# Schematic.net
KiCad netlist of a schematic drawn in EAGLE
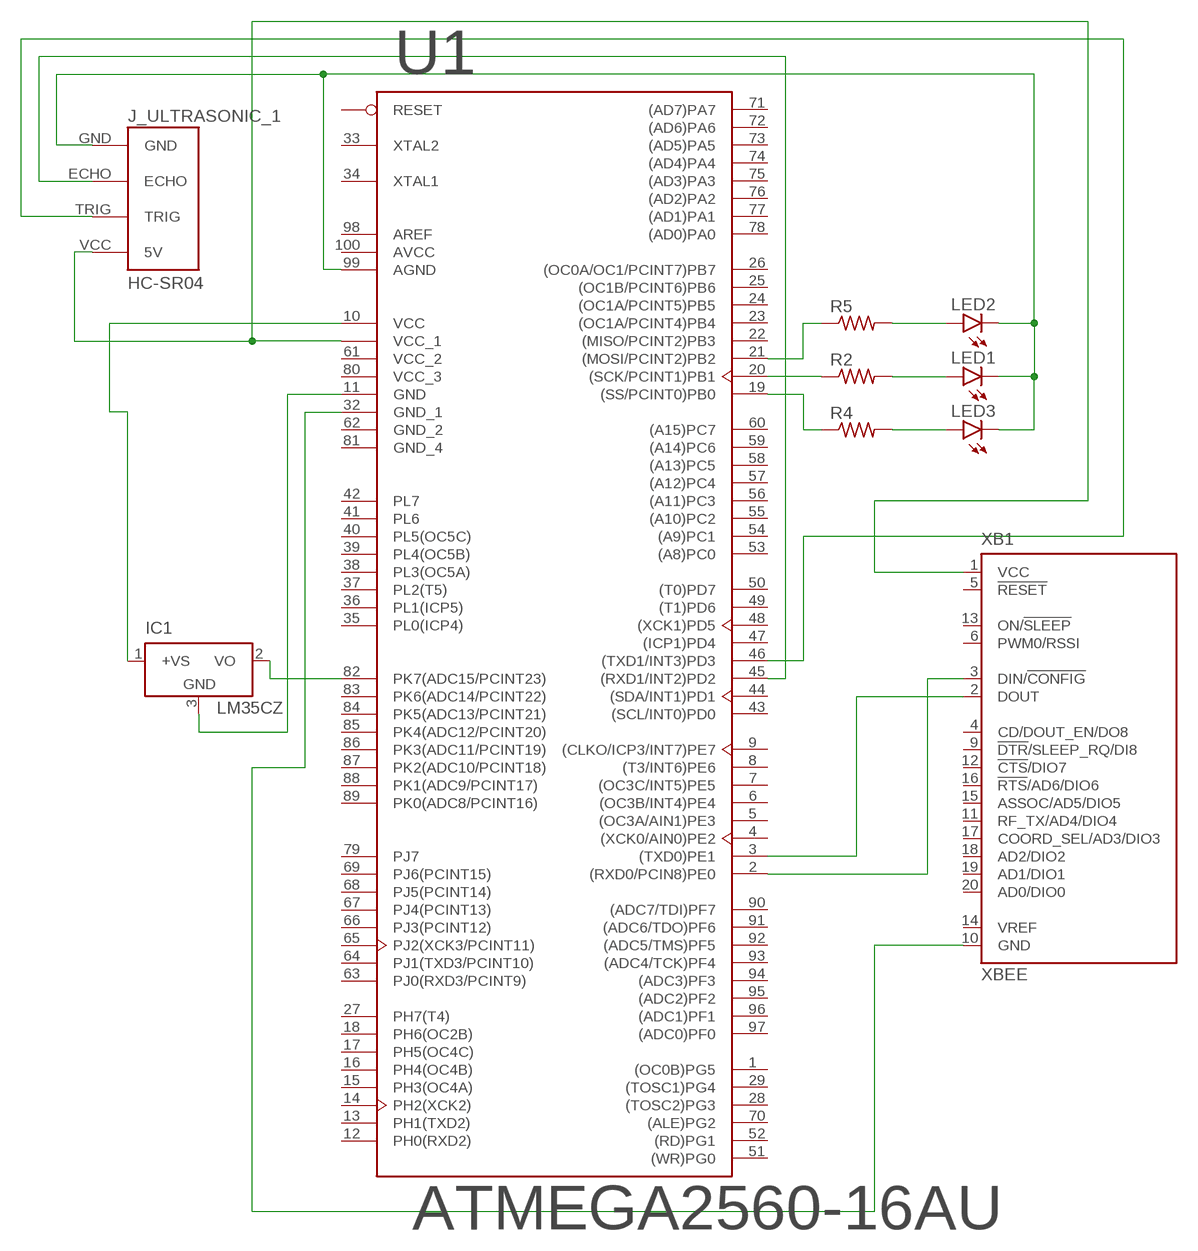
[diagram p0: schematic, sheet 1]

(export (version "E")
  (design (tool "Eeschema 10.0.6"))
  (components
    (comp (ref "IC1")
      (value "LM35CZ")
      (footprint "eagle-import:TO92")
      (libsource (lib "eagle-import") (part "LM35CZ"))
    )
    (comp (ref "J_ULTRASONIC_1")
      (value "HC-SR04")
      (footprint "eagle-import:HC-SR04_FOOTPRINT")
      (libsource (lib "eagle-import") (part "HC-SR04"))
    )
    (comp (ref "LED1")
      (value "LED5MM")
      (footprint "eagle-import:LED5MM")
      (libsource (lib "eagle-import") (part "LED5MM"))
    )
    (comp (ref "LED2")
      (value "LED5MM")
      (footprint "eagle-import:LED5MM")
      (libsource (lib "eagle-import") (part "LED5MM"))
    )
    (comp (ref "LED3")
      (value "LED5MM")
      (footprint "eagle-import:LED5MM")
      (libsource (lib "eagle-import") (part "LED5MM"))
    )
    (comp (ref "R2")
      (value "R-US_0204/7")
      (footprint "eagle-import:0204_7")
      (libsource (lib "eagle-import") (part "R-US_0204/7"))
    )
    (comp (ref "R4")
      (value "R-US_0204/7")
      (footprint "eagle-import:0204_7")
      (libsource (lib "eagle-import") (part "R-US_0204/7"))
    )
    (comp (ref "R5")
      (value "R-US_0204/7")
      (footprint "eagle-import:0204_7")
      (libsource (lib "eagle-import") (part "R-US_0204/7"))
    )
    (comp (ref "U1")
      (value "ATMEGA2560-16AU")
      (footprint "eagle-import:TQFP-100")
      (fields
        (field (name "DIGIKEY_PART_NUMBER") "ATMEGA2560-16AU-ND")
        (field (name "MANUFACTURER") "Microchip Technology")
        (field (name "CREATED_BY") "PCBLayout.com")
      )
      (libsource (lib "eagle-import") (part "ATMEGA2560-16AU"))
    )
    (comp (ref "XB1")
      (value "XBEE")
      (footprint "eagle-import:XBEE")
      (fields (field (name "MPN") "XBP24-Z7UIT-004"))
      (libsource (lib "eagle-import") (part "XBEE"))
    )
  )
  (nets
    (net (code "1") (name "/AREF") (class "Default")
      (node (ref "U1") (pin "98") (pinfunction "AREF_98") (pintype "power_in"))
    )
    (net (code "2") (name "/AVCC") (class "Default")
      (node (ref "U1") (pin "100") (pinfunction "AVCC_100") (pintype "power_in"))
    )
    (net (code "3") (name "/GND_2") (class "Default")
      (node (ref "U1") (pin "62") (pinfunction "GND_2_62") (pintype "power_in"))
    )
    (net (code "4") (name "/GND_4") (class "Default")
      (node (ref "U1") (pin "81") (pinfunction "GND_4_81") (pintype "power_in"))
    )
    (net (code "5") (name "/RESET") (class "Default")
      (node (ref "U1") (pin "30") (pinfunction "RESET_30") (pintype "power_in"))
    )
    (net (code "6") (name "/VCC_2") (class "Default")
      (node (ref "U1") (pin "61") (pinfunction "VCC_2_61") (pintype "power_in"))
    )
    (net (code "7") (name "/VCC_3") (class "Default")
      (node (ref "U1") (pin "80") (pinfunction "VCC_3_80") (pintype "power_in"))
    )
    (net (code "8") (name "Net-(IC1-+VS)") (class "Default")
      (node (ref "IC1") (pin "1") (pinfunction "+VS_1") (pintype "input"))
      (node (ref "U1") (pin "10") (pinfunction "VCC_10") (pintype "power_in"))
    )
    (net (code "9") (name "Net-(IC1-GND)") (class "Default")
      (node (ref "IC1") (pin "3") (pinfunction "GND_3") (pintype "power_in"))
      (node (ref "U1") (pin "11") (pinfunction "GND_11") (pintype "power_in"))
    )
    (net (code "10") (name "Net-(IC1-VO)") (class "Default")
      (node (ref "IC1") (pin "2") (pinfunction "VO_2") (pintype "input"))
      (node (ref "U1") (pin "82") (pinfunction "PK7(ADC15/PCINT23)_82") (pintype "bidirectional"))
    )
    (net (code "11") (name "Net-(J_ULTRASONIC_1-5V)") (class "Default")
      (node (ref "J_ULTRASONIC_1") (pin "VCC") (pinfunction "5V_VCC") (pintype "bidirectional"))
      (node (ref "U1") (pin "31") (pinfunction "VCC_1_31") (pintype "power_in"))
      (node (ref "XB1") (pin "1") (pinfunction "VCC_1") (pintype "power_in"))
    )
    (net (code "12") (name "Net-(LED1-C)") (class "Default")
      (node (ref "J_ULTRASONIC_1") (pin "GND") (pinfunction "GND_GND") (pintype "bidirectional"))
      (node (ref "LED1") (pin "K") (pinfunction "C_K") (pintype "passive"))
      (node (ref "LED2") (pin "K") (pinfunction "C_K") (pintype "passive"))
      (node (ref "LED3") (pin "K") (pinfunction "C_K") (pintype "passive"))
      (node (ref "U1") (pin "99") (pinfunction "AGND_99") (pintype "power_in"))
    )
    (net (code "13") (name "Net-(LED1-PadA)") (class "Default")
      (node (ref "LED1") (pin "A") (pinfunction "A_A") (pintype "passive"))
      (node (ref "R2") (pin "2") (pinfunction "2_2") (pintype "passive"))
    )
    (net (code "14") (name "Net-(LED2-PadA)") (class "Default")
      (node (ref "LED2") (pin "A") (pinfunction "A_A") (pintype "passive"))
      (node (ref "R5") (pin "2") (pinfunction "2_2") (pintype "passive"))
    )
    (net (code "15") (name "Net-(LED3-PadA)") (class "Default")
      (node (ref "LED3") (pin "A") (pinfunction "A_A") (pintype "passive"))
      (node (ref "R4") (pin "2") (pinfunction "2_2") (pintype "passive"))
    )
    (net (code "16") (name "Net-(U1-(MOSI{slash}PCINT2)PB2)") (class "Default")
      (node (ref "R5") (pin "1") (pinfunction "1_1") (pintype "passive"))
      (node (ref "U1") (pin "21") (pinfunction "(MOSI/PCINT2)PB2_21") (pintype "bidirectional"))
    )
    (net (code "17") (name "Net-(U1-(RXD0{slash}PCIN8)PE0)") (class "Default")
      (node (ref "U1") (pin "2") (pinfunction "(RXD0/PCIN8)PE0_2") (pintype "bidirectional"))
      (node (ref "XB1") (pin "3") (pinfunction "DIN/~{CONFIG}_3") (pintype "input"))
    )
    (net (code "18") (name "Net-(U1-(RXD1{slash}INT2)PD2)") (class "Default")
      (node (ref "J_ULTRASONIC_1") (pin "ECHO") (pinfunction "ECHO_ECHO") (pintype "bidirectional"))
      (node (ref "U1") (pin "45") (pinfunction "(RXD1/INT2)PD2_45") (pintype "bidirectional"))
    )
    (net (code "19") (name "Net-(U1-(SCK{slash}PCINT1)PB1)") (class "Default")
      (node (ref "R2") (pin "1") (pinfunction "1_1") (pintype "passive"))
      (node (ref "U1") (pin "20") (pinfunction "(SCK/PCINT1)PB1_20") (pintype "bidirectional"))
    )
    (net (code "20") (name "Net-(U1-(SS{slash}PCINT0)PB0)") (class "Default")
      (node (ref "R4") (pin "1") (pinfunction "1_1") (pintype "passive"))
      (node (ref "U1") (pin "19") (pinfunction "(SS/PCINT0)PB0_19") (pintype "bidirectional"))
    )
    (net (code "21") (name "Net-(U1-(TXD0)PE1)") (class "Default")
      (node (ref "U1") (pin "3") (pinfunction "(TXD0)PE1_3") (pintype "bidirectional"))
      (node (ref "XB1") (pin "2") (pinfunction "DOUT_2") (pintype "output"))
    )
    (net (code "22") (name "Net-(U1-(TXD1{slash}INT3)PD3)") (class "Default")
      (node (ref "J_ULTRASONIC_1") (pin "TRIG") (pinfunction "TRIG_TRIG") (pintype "bidirectional"))
      (node (ref "U1") (pin "46") (pinfunction "(TXD1/INT3)PD3_46") (pintype "bidirectional"))
    )
    (net (code "23") (name "Net-(U1-GND_1)") (class "Default")
      (node (ref "U1") (pin "32") (pinfunction "GND_1_32") (pintype "power_in"))
      (node (ref "XB1") (pin "10") (pinfunction "GND_10") (pintype "power_in"))
    )
    (net (code "24") (name "unconnected-(U1-(A8)PC0-Pad53)") (class "Default")
      (node (ref "U1") (pin "53") (pinfunction "(A8)PC0_53") (pintype "bidirectional"))
    )
    (net (code "25") (name "unconnected-(U1-(A9)PC1-Pad54)") (class "Default")
      (node (ref "U1") (pin "54") (pinfunction "(A9)PC1_54") (pintype "bidirectional"))
    )
    (net (code "26") (name "unconnected-(U1-(A10)PC2-Pad55)") (class "Default")
      (node (ref "U1") (pin "55") (pinfunction "(A10)PC2_55") (pintype "bidirectional"))
    )
    (net (code "27") (name "unconnected-(U1-(A11)PC3-Pad56)") (class "Default")
      (node (ref "U1") (pin "56") (pinfunction "(A11)PC3_56") (pintype "bidirectional"))
    )
    (net (code "28") (name "unconnected-(U1-(A12)PC4-Pad57)") (class "Default")
      (node (ref "U1") (pin "57") (pinfunction "(A12)PC4_57") (pintype "bidirectional"))
    )
    (net (code "29") (name "unconnected-(U1-(A13)PC5-Pad58)") (class "Default")
      (node (ref "U1") (pin "58") (pinfunction "(A13)PC5_58") (pintype "bidirectional"))
    )
    (net (code "30") (name "unconnected-(U1-(A14)PC6-Pad59)") (class "Default")
      (node (ref "U1") (pin "59") (pinfunction "(A14)PC6_59") (pintype "bidirectional"))
    )
    (net (code "31") (name "unconnected-(U1-(A15)PC7-Pad60)") (class "Default")
      (node (ref "U1") (pin "60") (pinfunction "(A15)PC7_60") (pintype "bidirectional"))
    )
    (net (code "32") (name "unconnected-(U1-(AD0)PA0-Pad78)") (class "Default")
      (node (ref "U1") (pin "78") (pinfunction "(AD0)PA0_78") (pintype "bidirectional"))
    )
    (net (code "33") (name "unconnected-(U1-(AD1)PA1-Pad77)") (class "Default")
      (node (ref "U1") (pin "77") (pinfunction "(AD1)PA1_77") (pintype "bidirectional"))
    )
    (net (code "34") (name "unconnected-(U1-(AD2)PA2-Pad76)") (class "Default")
      (node (ref "U1") (pin "76") (pinfunction "(AD2)PA2_76") (pintype "bidirectional"))
    )
    (net (code "35") (name "unconnected-(U1-(AD3)PA3-Pad75)") (class "Default")
      (node (ref "U1") (pin "75") (pinfunction "(AD3)PA3_75") (pintype "bidirectional"))
    )
    (net (code "36") (name "unconnected-(U1-(AD4)PA4-Pad74)") (class "Default")
      (node (ref "U1") (pin "74") (pinfunction "(AD4)PA4_74") (pintype "bidirectional"))
    )
    (net (code "37") (name "unconnected-(U1-(AD5)PA5-Pad73)") (class "Default")
      (node (ref "U1") (pin "73") (pinfunction "(AD5)PA5_73") (pintype "bidirectional"))
    )
    (net (code "38") (name "unconnected-(U1-(AD6)PA6-Pad72)") (class "Default")
      (node (ref "U1") (pin "72") (pinfunction "(AD6)PA6_72") (pintype "bidirectional"))
    )
    (net (code "39") (name "unconnected-(U1-(AD7)PA7-Pad71)") (class "Default")
      (node (ref "U1") (pin "71") (pinfunction "(AD7)PA7_71") (pintype "bidirectional"))
    )
    (net (code "40") (name "unconnected-(U1-(ADC0)PF0-Pad97)") (class "Default")
      (node (ref "U1") (pin "97") (pinfunction "(ADC0)PF0_97") (pintype "bidirectional"))
    )
    (net (code "41") (name "unconnected-(U1-(ADC1)PF1-Pad96)") (class "Default")
      (node (ref "U1") (pin "96") (pinfunction "(ADC1)PF1_96") (pintype "bidirectional"))
    )
    (net (code "42") (name "unconnected-(U1-(ADC2)PF2-Pad95)") (class "Default")
      (node (ref "U1") (pin "95") (pinfunction "(ADC2)PF2_95") (pintype "bidirectional"))
    )
    (net (code "43") (name "unconnected-(U1-(ADC3)PF3-Pad94)") (class "Default")
      (node (ref "U1") (pin "94") (pinfunction "(ADC3)PF3_94") (pintype "bidirectional"))
    )
    (net (code "44") (name "unconnected-(U1-(ADC4{slash}TCK)PF4-Pad93)") (class "Default")
      (node (ref "U1") (pin "93") (pinfunction "(ADC4/TCK)PF4_93") (pintype "bidirectional"))
    )
    (net (code "45") (name "unconnected-(U1-(ADC5{slash}TMS)PF5-Pad92)") (class "Default")
      (node (ref "U1") (pin "92") (pinfunction "(ADC5/TMS)PF5_92") (pintype "bidirectional"))
    )
    (net (code "46") (name "unconnected-(U1-(ADC6{slash}TDO)PF6-Pad91)") (class "Default")
      (node (ref "U1") (pin "91") (pinfunction "(ADC6/TDO)PF6_91") (pintype "bidirectional"))
    )
    (net (code "47") (name "unconnected-(U1-(ADC7{slash}TDI)PF7-Pad90)") (class "Default")
      (node (ref "U1") (pin "90") (pinfunction "(ADC7/TDI)PF7_90") (pintype "bidirectional"))
    )
    (net (code "48") (name "unconnected-(U1-(ALE)PG2-Pad70)") (class "Default")
      (node (ref "U1") (pin "70") (pinfunction "(ALE)PG2_70") (pintype "bidirectional"))
    )
    (net (code "49") (name "unconnected-(U1-(CLKO{slash}ICP3{slash}INT7)PE7-Pad9)") (class "Default")
      (node (ref "U1") (pin "9") (pinfunction "(CLKO/ICP3/INT7)PE7_9") (pintype "bidirectional"))
    )
    (net (code "50") (name "unconnected-(U1-(ICP1)PD4-Pad47)") (class "Default")
      (node (ref "U1") (pin "47") (pinfunction "(ICP1)PD4_47") (pintype "bidirectional"))
    )
    (net (code "51") (name "unconnected-(U1-(MISO{slash}PCINT2)PB3-Pad22)") (class "Default")
      (node (ref "U1") (pin "22") (pinfunction "(MISO/PCINT2)PB3_22") (pintype "bidirectional"))
    )
    (net (code "52") (name "unconnected-(U1-(OC0A{slash}OC1{slash}PCINT7)PB7-Pad26)") (class "Default")
      (node (ref "U1") (pin "26") (pinfunction "(OC0A/OC1/PCINT7)PB7_26") (pintype "bidirectional"))
    )
    (net (code "53") (name "unconnected-(U1-(OC0B)PG5-Pad1)") (class "Default")
      (node (ref "U1") (pin "1") (pinfunction "(OC0B)PG5_1") (pintype "bidirectional"))
    )
    (net (code "54") (name "unconnected-(U1-(OC1A{slash}PCINT4)PB4-Pad23)") (class "Default")
      (node (ref "U1") (pin "23") (pinfunction "(OC1A/PCINT4)PB4_23") (pintype "bidirectional"))
    )
    (net (code "55") (name "unconnected-(U1-(OC1A{slash}PCINT5)PB5-Pad24)") (class "Default")
      (node (ref "U1") (pin "24") (pinfunction "(OC1A/PCINT5)PB5_24") (pintype "bidirectional"))
    )
    (net (code "56") (name "unconnected-(U1-(OC1B{slash}PCINT6)PB6-Pad25)") (class "Default")
      (node (ref "U1") (pin "25") (pinfunction "(OC1B/PCINT6)PB6_25") (pintype "bidirectional"))
    )
    (net (code "57") (name "unconnected-(U1-(OC3A{slash}AIN1)PE3-Pad5)") (class "Default")
      (node (ref "U1") (pin "5") (pinfunction "(OC3A/AIN1)PE3_5") (pintype "bidirectional"))
    )
    (net (code "58") (name "unconnected-(U1-(OC3B{slash}INT4)PE4-Pad6)") (class "Default")
      (node (ref "U1") (pin "6") (pinfunction "(OC3B/INT4)PE4_6") (pintype "bidirectional"))
    )
    (net (code "59") (name "unconnected-(U1-(OC3C{slash}INT5)PE5-Pad7)") (class "Default")
      (node (ref "U1") (pin "7") (pinfunction "(OC3C/INT5)PE5_7") (pintype "bidirectional"))
    )
    (net (code "60") (name "unconnected-(U1-(RD)PG1-Pad52)") (class "Default")
      (node (ref "U1") (pin "52") (pinfunction "(RD)PG1_52") (pintype "bidirectional"))
    )
    (net (code "61") (name "unconnected-(U1-(SCL{slash}INT0)PD0-Pad43)") (class "Default")
      (node (ref "U1") (pin "43") (pinfunction "(SCL/INT0)PD0_43") (pintype "bidirectional"))
    )
    (net (code "62") (name "unconnected-(U1-(SDA{slash}INT1)PD1-Pad44)") (class "Default")
      (node (ref "U1") (pin "44") (pinfunction "(SDA/INT1)PD1_44") (pintype "bidirectional"))
    )
    (net (code "63") (name "unconnected-(U1-(T0)PD7-Pad50)") (class "Default")
      (node (ref "U1") (pin "50") (pinfunction "(T0)PD7_50") (pintype "bidirectional"))
    )
    (net (code "64") (name "unconnected-(U1-(T1)PD6-Pad49)") (class "Default")
      (node (ref "U1") (pin "49") (pinfunction "(T1)PD6_49") (pintype "bidirectional"))
    )
    (net (code "65") (name "unconnected-(U1-(T3{slash}INT6)PE6-Pad8)") (class "Default")
      (node (ref "U1") (pin "8") (pinfunction "(T3/INT6)PE6_8") (pintype "bidirectional"))
    )
    (net (code "66") (name "unconnected-(U1-(TOSC1)PG4-Pad29)") (class "Default")
      (node (ref "U1") (pin "29") (pinfunction "(TOSC1)PG4_29") (pintype "bidirectional"))
    )
    (net (code "67") (name "unconnected-(U1-(TOSC2)PG3-Pad28)") (class "Default")
      (node (ref "U1") (pin "28") (pinfunction "(TOSC2)PG3_28") (pintype "bidirectional"))
    )
    (net (code "68") (name "unconnected-(U1-(WR)PG0-Pad51)") (class "Default")
      (node (ref "U1") (pin "51") (pinfunction "(WR)PG0_51") (pintype "bidirectional"))
    )
    (net (code "69") (name "unconnected-(U1-(XCK0{slash}AIN0)PE2-Pad4)") (class "Default")
      (node (ref "U1") (pin "4") (pinfunction "(XCK0/AIN0)PE2_4") (pintype "bidirectional"))
    )
    (net (code "70") (name "unconnected-(U1-(XCK1)PD5-Pad48)") (class "Default")
      (node (ref "U1") (pin "48") (pinfunction "(XCK1)PD5_48") (pintype "bidirectional"))
    )
    (net (code "71") (name "unconnected-(U1-PH0(RXD2)-Pad12)") (class "Default")
      (node (ref "U1") (pin "12") (pinfunction "PH0(RXD2)_12") (pintype "bidirectional"))
    )
    (net (code "72") (name "unconnected-(U1-PH1(TXD2)-Pad13)") (class "Default")
      (node (ref "U1") (pin "13") (pinfunction "PH1(TXD2)_13") (pintype "bidirectional"))
    )
    (net (code "73") (name "unconnected-(U1-PH2(XCK2)-Pad14)") (class "Default")
      (node (ref "U1") (pin "14") (pinfunction "PH2(XCK2)_14") (pintype "bidirectional"))
    )
    (net (code "74") (name "unconnected-(U1-PH3(OC4A)-Pad15)") (class "Default")
      (node (ref "U1") (pin "15") (pinfunction "PH3(OC4A)_15") (pintype "bidirectional"))
    )
    (net (code "75") (name "unconnected-(U1-PH4(OC4B)-Pad16)") (class "Default")
      (node (ref "U1") (pin "16") (pinfunction "PH4(OC4B)_16") (pintype "bidirectional"))
    )
    (net (code "76") (name "unconnected-(U1-PH5(OC4C)-Pad17)") (class "Default")
      (node (ref "U1") (pin "17") (pinfunction "PH5(OC4C)_17") (pintype "bidirectional"))
    )
    (net (code "77") (name "unconnected-(U1-PH6(OC2B)-Pad18)") (class "Default")
      (node (ref "U1") (pin "18") (pinfunction "PH6(OC2B)_18") (pintype "bidirectional"))
    )
    (net (code "78") (name "unconnected-(U1-PH7(T4)-Pad27)") (class "Default")
      (node (ref "U1") (pin "27") (pinfunction "PH7(T4)_27") (pintype "bidirectional"))
    )
    (net (code "79") (name "unconnected-(U1-PJ0(RXD3{slash}PCINT9)-Pad63)") (class "Default")
      (node (ref "U1") (pin "63") (pinfunction "PJ0(RXD3/PCINT9)_63") (pintype "bidirectional"))
    )
    (net (code "80") (name "unconnected-(U1-PJ1(TXD3{slash}PCINT10)-Pad64)") (class "Default")
      (node (ref "U1") (pin "64") (pinfunction "PJ1(TXD3/PCINT10)_64") (pintype "bidirectional"))
    )
    (net (code "81") (name "unconnected-(U1-PJ2(XCK3{slash}PCINT11)-Pad65)") (class "Default")
      (node (ref "U1") (pin "65") (pinfunction "PJ2(XCK3/PCINT11)_65") (pintype "bidirectional"))
    )
    (net (code "82") (name "unconnected-(U1-PJ3(PCINT12)-Pad66)") (class "Default")
      (node (ref "U1") (pin "66") (pinfunction "PJ3(PCINT12)_66") (pintype "bidirectional"))
    )
    (net (code "83") (name "unconnected-(U1-PJ4(PCINT13)-Pad67)") (class "Default")
      (node (ref "U1") (pin "67") (pinfunction "PJ4(PCINT13)_67") (pintype "bidirectional"))
    )
    (net (code "84") (name "unconnected-(U1-PJ5(PCINT14)-Pad68)") (class "Default")
      (node (ref "U1") (pin "68") (pinfunction "PJ5(PCINT14)_68") (pintype "bidirectional"))
    )
    (net (code "85") (name "unconnected-(U1-PJ6(PCINT15)-Pad69)") (class "Default")
      (node (ref "U1") (pin "69") (pinfunction "PJ6(PCINT15)_69") (pintype "bidirectional"))
    )
    (net (code "86") (name "unconnected-(U1-PJ7-Pad79)") (class "Default")
      (node (ref "U1") (pin "79") (pinfunction "PJ7_79") (pintype "bidirectional"))
    )
    (net (code "87") (name "unconnected-(U1-PK0(ADC8{slash}PCINT16)-Pad89)") (class "Default")
      (node (ref "U1") (pin "89") (pinfunction "PK0(ADC8/PCINT16)_89") (pintype "bidirectional"))
    )
    (net (code "88") (name "unconnected-(U1-PK1(ADC9{slash}PCINT17)-Pad88)") (class "Default")
      (node (ref "U1") (pin "88") (pinfunction "PK1(ADC9/PCINT17)_88") (pintype "bidirectional"))
    )
    (net (code "89") (name "unconnected-(U1-PK2(ADC10{slash}PCINT18)-Pad87)") (class "Default")
      (node (ref "U1") (pin "87") (pinfunction "PK2(ADC10/PCINT18)_87") (pintype "bidirectional"))
    )
    (net (code "90") (name "unconnected-(U1-PK3(ADC11{slash}PCINT19)-Pad86)") (class "Default")
      (node (ref "U1") (pin "86") (pinfunction "PK3(ADC11/PCINT19)_86") (pintype "bidirectional"))
    )
    (net (code "91") (name "unconnected-(U1-PK4(ADC12{slash}PCINT20)-Pad85)") (class "Default")
      (node (ref "U1") (pin "85") (pinfunction "PK4(ADC12/PCINT20)_85") (pintype "bidirectional"))
    )
    (net (code "92") (name "unconnected-(U1-PK5(ADC13{slash}PCINT21)-Pad84)") (class "Default")
      (node (ref "U1") (pin "84") (pinfunction "PK5(ADC13/PCINT21)_84") (pintype "bidirectional"))
    )
    (net (code "93") (name "unconnected-(U1-PK6(ADC14{slash}PCINT22)-Pad83)") (class "Default")
      (node (ref "U1") (pin "83") (pinfunction "PK6(ADC14/PCINT22)_83") (pintype "bidirectional"))
    )
    (net (code "94") (name "unconnected-(U1-PL0(ICP4)-Pad35)") (class "Default")
      (node (ref "U1") (pin "35") (pinfunction "PL0(ICP4)_35") (pintype "bidirectional"))
    )
    (net (code "95") (name "unconnected-(U1-PL1(ICP5)-Pad36)") (class "Default")
      (node (ref "U1") (pin "36") (pinfunction "PL1(ICP5)_36") (pintype "bidirectional"))
    )
    (net (code "96") (name "unconnected-(U1-PL2(T5)-Pad37)") (class "Default")
      (node (ref "U1") (pin "37") (pinfunction "PL2(T5)_37") (pintype "bidirectional"))
    )
    (net (code "97") (name "unconnected-(U1-PL3(OC5A)-Pad38)") (class "Default")
      (node (ref "U1") (pin "38") (pinfunction "PL3(OC5A)_38") (pintype "bidirectional"))
    )
    (net (code "98") (name "unconnected-(U1-PL4(OC5B)-Pad39)") (class "Default")
      (node (ref "U1") (pin "39") (pinfunction "PL4(OC5B)_39") (pintype "bidirectional"))
    )
    (net (code "99") (name "unconnected-(U1-PL5(OC5C)-Pad40)") (class "Default")
      (node (ref "U1") (pin "40") (pinfunction "PL5(OC5C)_40") (pintype "bidirectional"))
    )
    (net (code "100") (name "unconnected-(U1-PL6-Pad41)") (class "Default")
      (node (ref "U1") (pin "41") (pinfunction "PL6_41") (pintype "bidirectional"))
    )
    (net (code "101") (name "unconnected-(U1-PL7-Pad42)") (class "Default")
      (node (ref "U1") (pin "42") (pinfunction "PL7_42") (pintype "bidirectional"))
    )
    (net (code "102") (name "unconnected-(U1-XTAL1-Pad34)") (class "Default")
      (node (ref "U1") (pin "34") (pinfunction "XTAL1_34") (pintype "passive"))
    )
    (net (code "103") (name "unconnected-(U1-XTAL2-Pad33)") (class "Default")
      (node (ref "U1") (pin "33") (pinfunction "XTAL2_33") (pintype "passive"))
    )
    (net (code "104") (name "unconnected-(XB1-AD0{slash}DIO0-Pad20)") (class "Default")
      (node (ref "XB1") (pin "20") (pinfunction "AD0/DIO0_20") (pintype "bidirectional"))
    )
    (net (code "105") (name "unconnected-(XB1-AD1{slash}DIO1-Pad19)") (class "Default")
      (node (ref "XB1") (pin "19") (pinfunction "AD1/DIO1_19") (pintype "bidirectional"))
    )
    (net (code "106") (name "unconnected-(XB1-AD2{slash}DIO2-Pad18)") (class "Default")
      (node (ref "XB1") (pin "18") (pinfunction "AD2/DIO2_18") (pintype "bidirectional"))
    )
    (net (code "107") (name "unconnected-(XB1-ASSOC{slash}AD5{slash}DIO5-Pad15)") (class "Default")
      (node (ref "XB1") (pin "15") (pinfunction "ASSOC/AD5/DIO5_15") (pintype "bidirectional"))
    )
    (net (code "108") (name "unconnected-(XB1-CD{slash}DOUT_EN{slash}DO8-Pad4)") (class "Default")
      (node (ref "XB1") (pin "4") (pinfunction "CD/DOUT_EN/DO8_4") (pintype "output"))
    )
    (net (code "109") (name "unconnected-(XB1-COORD_SEL{slash}AD3{slash}DIO3-Pad17)") (class "Default")
      (node (ref "XB1") (pin "17") (pinfunction "COORD_SEL/AD3/DIO3_17") (pintype "bidirectional"))
    )
    (net (code "110") (name "unconnected-(XB1-ON{slash}~{SLEEP}-Pad13)") (class "Default")
      (node (ref "XB1") (pin "13") (pinfunction "ON/~{SLEEP}_13") (pintype "output"))
    )
    (net (code "111") (name "unconnected-(XB1-PWM0{slash}RSSI-Pad6)") (class "Default")
      (node (ref "XB1") (pin "6") (pinfunction "PWM0/RSSI_6") (pintype "output"))
    )
    (net (code "112") (name "unconnected-(XB1-RF_TX{slash}AD4{slash}DIO4-Pad11)") (class "Default")
      (node (ref "XB1") (pin "11") (pinfunction "RF_TX/AD4/DIO4_11") (pintype "bidirectional"))
    )
    (net (code "113") (name "unconnected-(XB1-VREF-Pad14)") (class "Default")
      (node (ref "XB1") (pin "14") (pinfunction "VREF_14") (pintype "input"))
    )
    (net (code "114") (name "unconnected-(XB1-~{CTS}{slash}DIO7-Pad12)") (class "Default")
      (node (ref "XB1") (pin "12") (pinfunction "~{CTS}/DIO7_12") (pintype "bidirectional"))
    )
    (net (code "115") (name "unconnected-(XB1-~{DTR}{slash}SLEEP_RQ{slash}DI8-Pad9)") (class "Default")
      (node (ref "XB1") (pin "9") (pinfunction "~{DTR}/SLEEP_RQ/DI8_9") (pintype "bidirectional"))
    )
    (net (code "116") (name "unconnected-(XB1-~{RESET}-Pad5)") (class "Default")
      (node (ref "XB1") (pin "5") (pinfunction "~{RESET}_5") (pintype "input"))
    )
    (net (code "117") (name "unconnected-(XB1-~{RTS}{slash}AD6{slash}DIO6-Pad16)") (class "Default")
      (node (ref "XB1") (pin "16") (pinfunction "~{RTS}/AD6/DIO6_16") (pintype "bidirectional"))
    )
  )
)
